# FEU31_Part2.net
KiCad netlist of a schematic drawn in Altium Designer
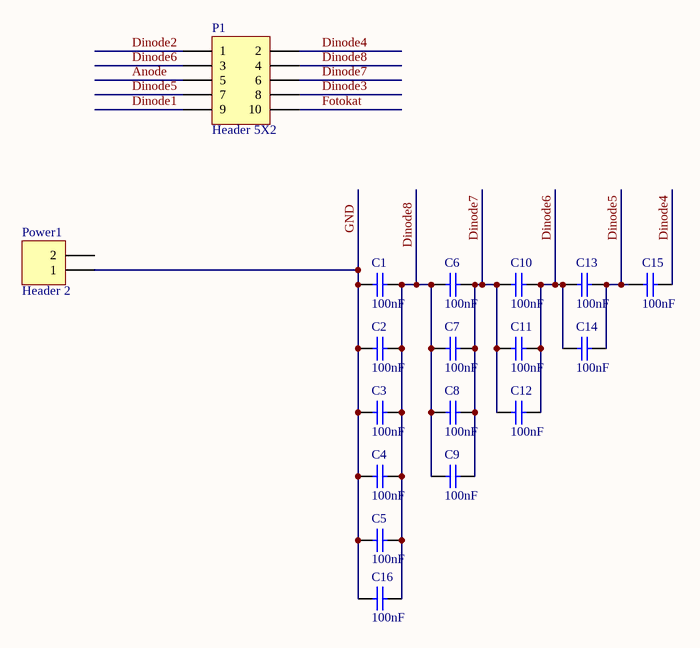
[diagram p0: FEU31_Part2.SchDoc]

(export (version "E")
  (design (tool "Eeschema 10.0.6"))
  (components
    (comp (ref "C1")
      (value "100nF")
      (footprint "Miscellaneous Devices:C1206")
      (description "Capacitor (Semiconductor SIM Model)")
      (fields (field (name "PUBLISHER") "Altium Limited"))
      (libsource (lib "Miscellaneous Devices") (part "Cap Semi"))
    )
    (comp (ref "C2")
      (value "100nF")
      (footprint "Miscellaneous Devices:C1206")
      (description "Capacitor (Semiconductor SIM Model)")
      (fields (field (name "PUBLISHER") "Altium Limited"))
      (libsource (lib "Miscellaneous Devices") (part "Cap Semi"))
    )
    (comp (ref "C3")
      (value "100nF")
      (footprint "Miscellaneous Devices:C1206")
      (description "Capacitor (Semiconductor SIM Model)")
      (fields (field (name "PUBLISHER") "Altium Limited"))
      (libsource (lib "Miscellaneous Devices") (part "Cap Semi"))
    )
    (comp (ref "C4")
      (value "100nF")
      (footprint "Miscellaneous Devices:C1206")
      (description "Capacitor (Semiconductor SIM Model)")
      (fields (field (name "PUBLISHER") "Altium Limited"))
      (libsource (lib "Miscellaneous Devices") (part "Cap Semi"))
    )
    (comp (ref "C5")
      (value "100nF")
      (footprint "Miscellaneous Devices:C1206")
      (description "Capacitor (Semiconductor SIM Model)")
      (fields (field (name "PUBLISHER") "Altium Limited"))
      (libsource (lib "Miscellaneous Devices") (part "Cap Semi"))
    )
    (comp (ref "C6")
      (value "100nF")
      (footprint "Miscellaneous Devices:C1206")
      (description "Capacitor (Semiconductor SIM Model)")
      (fields (field (name "PUBLISHER") "Altium Limited"))
      (libsource (lib "Miscellaneous Devices") (part "Cap Semi"))
    )
    (comp (ref "C7")
      (value "100nF")
      (footprint "Miscellaneous Devices:C1206")
      (description "Capacitor (Semiconductor SIM Model)")
      (fields (field (name "PUBLISHER") "Altium Limited"))
      (libsource (lib "Miscellaneous Devices") (part "Cap Semi"))
    )
    (comp (ref "C8")
      (value "100nF")
      (footprint "Miscellaneous Devices:C1206")
      (description "Capacitor (Semiconductor SIM Model)")
      (fields (field (name "PUBLISHER") "Altium Limited"))
      (libsource (lib "Miscellaneous Devices") (part "Cap Semi"))
    )
    (comp (ref "C9")
      (value "100nF")
      (footprint "Miscellaneous Devices:C1206")
      (description "Capacitor (Semiconductor SIM Model)")
      (fields (field (name "PUBLISHER") "Altium Limited"))
      (libsource (lib "Miscellaneous Devices") (part "Cap Semi"))
    )
    (comp (ref "C10")
      (value "100nF")
      (footprint "Miscellaneous Devices:C1206")
      (description "Capacitor (Semiconductor SIM Model)")
      (fields (field (name "PUBLISHER") "Altium Limited"))
      (libsource (lib "Miscellaneous Devices") (part "Cap Semi"))
    )
    (comp (ref "C11")
      (value "100nF")
      (footprint "Miscellaneous Devices:C1206")
      (description "Capacitor (Semiconductor SIM Model)")
      (fields (field (name "PUBLISHER") "Altium Limited"))
      (libsource (lib "Miscellaneous Devices") (part "Cap Semi"))
    )
    (comp (ref "C12")
      (value "100nF")
      (footprint "Miscellaneous Devices:C1206")
      (description "Capacitor (Semiconductor SIM Model)")
      (fields (field (name "PUBLISHER") "Altium Limited"))
      (libsource (lib "Miscellaneous Devices") (part "Cap Semi"))
    )
    (comp (ref "C13")
      (value "100nF")
      (footprint "Miscellaneous Devices:C1206")
      (description "Capacitor (Semiconductor SIM Model)")
      (fields (field (name "PUBLISHER") "Altium Limited"))
      (libsource (lib "Miscellaneous Devices") (part "Cap Semi"))
    )
    (comp (ref "C14")
      (value "100nF")
      (footprint "Miscellaneous Devices:C1206")
      (description "Capacitor (Semiconductor SIM Model)")
      (fields (field (name "PUBLISHER") "Altium Limited"))
      (libsource (lib "Miscellaneous Devices") (part "Cap Semi"))
    )
    (comp (ref "C15")
      (value "100nF")
      (footprint "Miscellaneous Devices:C1206")
      (description "Capacitor (Semiconductor SIM Model)")
      (fields (field (name "PUBLISHER") "Altium Limited"))
      (libsource (lib "Miscellaneous Devices") (part "Cap Semi"))
    )
    (comp (ref "C16")
      (value "100nF")
      (footprint "Miscellaneous Devices:C1206")
      (description "Capacitor (Semiconductor SIM Model)")
      (fields (field (name "PUBLISHER") "Altium Limited"))
      (libsource (lib "Miscellaneous Devices") (part "Cap Semi"))
    )
    (comp (ref "P1")
      (value "Header 5X2")
      (footprint "ФЭУ-31")
      (description "Header, 5-Pin, Dual row")
      (fields (field (name "PUBLISHER") "Altium Limited"))
      (libsource (lib "Miscellaneous Connectors") (part "Header 5X2"))
    )
    (comp (ref "Power1")
      (value "Header 2")
      (footprint "HDR1X2")
      (description "Header, 2-Pin")
      (fields (field (name "PUBLISHER") "Altium Limited"))
      (libsource (lib "Miscellaneous Connectors") (part "Header 2"))
    )
  )
  (nets
    (net (code "1") (name "/Anode") (class "Default")
      (node (ref "P1") (pin "5") (pinfunction "5_5") (pintype "passive"))
    )
    (net (code "2") (name "/Dinode1") (class "Default")
      (node (ref "P1") (pin "9") (pinfunction "9_9") (pintype "passive"))
    )
    (net (code "3") (name "/Dinode2") (class "Default")
      (node (ref "P1") (pin "1") (pinfunction "1_1") (pintype "passive"))
    )
    (net (code "4") (name "/Dinode3") (class "Default")
      (node (ref "P1") (pin "8") (pinfunction "8_8") (pintype "passive"))
    )
    (net (code "5") (name "/Dinode4") (class "Default")
      (node (ref "C15") (pin "1") (pinfunction "1_1") (pintype "passive"))
      (node (ref "P1") (pin "2") (pinfunction "2_2") (pintype "passive"))
    )
    (net (code "6") (name "/Dinode5") (class "Default")
      (node (ref "C13") (pin "1") (pinfunction "1_1") (pintype "passive"))
      (node (ref "C14") (pin "1") (pinfunction "1_1") (pintype "passive"))
      (node (ref "C15") (pin "2") (pinfunction "2_2") (pintype "passive"))
      (node (ref "P1") (pin "7") (pinfunction "7_7") (pintype "passive"))
    )
    (net (code "7") (name "/Dinode6") (class "Default")
      (node (ref "C10") (pin "1") (pinfunction "1_1") (pintype "passive"))
      (node (ref "C11") (pin "1") (pinfunction "1_1") (pintype "passive"))
      (node (ref "C12") (pin "1") (pinfunction "1_1") (pintype "passive"))
      (node (ref "C13") (pin "2") (pinfunction "2_2") (pintype "passive"))
      (node (ref "C14") (pin "2") (pinfunction "2_2") (pintype "passive"))
      (node (ref "P1") (pin "3") (pinfunction "3_3") (pintype "passive"))
    )
    (net (code "8") (name "/Dinode7") (class "Default")
      (node (ref "C10") (pin "2") (pinfunction "2_2") (pintype "passive"))
      (node (ref "C11") (pin "2") (pinfunction "2_2") (pintype "passive"))
      (node (ref "C12") (pin "2") (pinfunction "2_2") (pintype "passive"))
      (node (ref "C6") (pin "1") (pinfunction "1_1") (pintype "passive"))
      (node (ref "C7") (pin "1") (pinfunction "1_1") (pintype "passive"))
      (node (ref "C8") (pin "1") (pinfunction "1_1") (pintype "passive"))
      (node (ref "C9") (pin "1") (pinfunction "1_1") (pintype "passive"))
      (node (ref "P1") (pin "6") (pinfunction "6_6") (pintype "passive"))
    )
    (net (code "9") (name "/Dinode8") (class "Default")
      (node (ref "C1") (pin "1") (pinfunction "1_1") (pintype "passive"))
      (node (ref "C16") (pin "1") (pinfunction "1_1") (pintype "passive"))
      (node (ref "C2") (pin "1") (pinfunction "1_1") (pintype "passive"))
      (node (ref "C3") (pin "1") (pinfunction "1_1") (pintype "passive"))
      (node (ref "C4") (pin "1") (pinfunction "1_1") (pintype "passive"))
      (node (ref "C5") (pin "1") (pinfunction "1_1") (pintype "passive"))
      (node (ref "C6") (pin "2") (pinfunction "2_2") (pintype "passive"))
      (node (ref "C7") (pin "2") (pinfunction "2_2") (pintype "passive"))
      (node (ref "C8") (pin "2") (pinfunction "2_2") (pintype "passive"))
      (node (ref "C9") (pin "2") (pinfunction "2_2") (pintype "passive"))
      (node (ref "P1") (pin "4") (pinfunction "4_4") (pintype "passive"))
    )
    (net (code "10") (name "/Fotokat") (class "Default")
      (node (ref "P1") (pin "10") (pinfunction "10_10") (pintype "passive"))
    )
    (net (code "11") (name "/GND") (class "Default")
      (node (ref "C1") (pin "2") (pinfunction "2_2") (pintype "passive"))
      (node (ref "C16") (pin "2") (pinfunction "2_2") (pintype "passive"))
      (node (ref "C2") (pin "2") (pinfunction "2_2") (pintype "passive"))
      (node (ref "C3") (pin "2") (pinfunction "2_2") (pintype "passive"))
      (node (ref "C4") (pin "2") (pinfunction "2_2") (pintype "passive"))
      (node (ref "C5") (pin "2") (pinfunction "2_2") (pintype "passive"))
      (node (ref "Power1") (pin "1") (pinfunction "1_1") (pintype "passive"))
    )
    (net (code "12") (name "unconnected-(Power1-Pad2)") (class "Default")
      (node (ref "Power1") (pin "2") (pinfunction "2_2") (pintype "passive"))
    )
  )
)
